# Multiplexer_Bank.net
KiCad netlist of a schematic drawn in Altium Designer
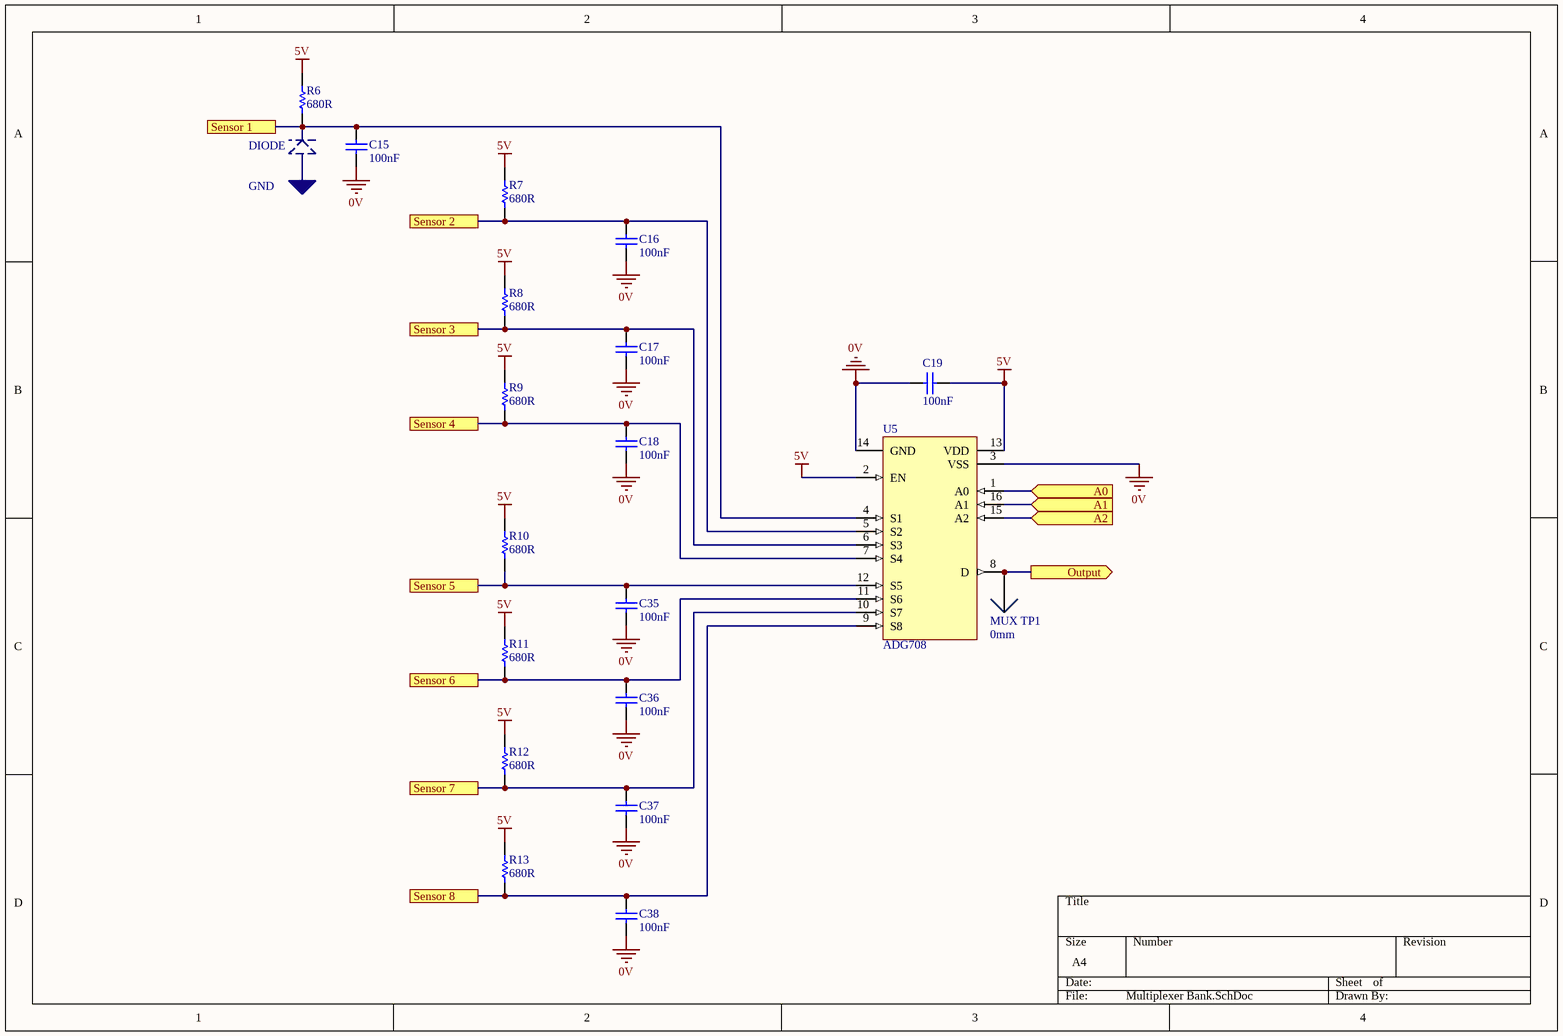
[diagram p0: Multiplexer Bank.SchDoc]

(export (version "E")
  (design (tool "Eeschema 10.0.6"))
  (components
    (comp (ref "C15")
      (value "100nF")
      (footprint "0805")
      (fields
        (field (name "PART NUMBER") "GCM21BR71E104KA37L")
        (field (name "TOLERANCE") "10%")
        (field (name "MANUFACTURER") "muRata")
      )
      (libsource (lib "ts_20-standard-library") (part "Capacitor"))
    )
    (comp (ref "C16")
      (value "100nF")
      (footprint "0805")
      (fields
        (field (name "PART NUMBER") "GCM21BR71E104KA37L")
        (field (name "TOLERANCE") "10%")
        (field (name "MANUFACTURER") "muRata")
      )
      (libsource (lib "ts_20-standard-library") (part "Capacitor"))
    )
    (comp (ref "C17")
      (value "100nF")
      (footprint "0805")
      (fields
        (field (name "PART NUMBER") "GCM21BR71E104KA37L")
        (field (name "TOLERANCE") "10%")
        (field (name "MANUFACTURER") "muRata")
      )
      (libsource (lib "ts_20-standard-library") (part "Capacitor"))
    )
    (comp (ref "C18")
      (value "100nF")
      (footprint "0805")
      (fields
        (field (name "PART NUMBER") "GCM21BR71E104KA37L")
        (field (name "TOLERANCE") "10%")
        (field (name "MANUFACTURER") "muRata")
      )
      (libsource (lib "ts_20-standard-library") (part "Capacitor"))
    )
    (comp (ref "C19")
      (value "100nF")
      (footprint "0805")
      (fields
        (field (name "PART NUMBER") "GCM21BR71E104KA37L")
        (field (name "TOLERANCE") "10%")
        (field (name "MANUFACTURER") "muRata")
      )
      (libsource (lib "ts_20-standard-library") (part "Capacitor"))
    )
    (comp (ref "C35")
      (value "100nF")
      (footprint "0805")
      (fields
        (field (name "PART NUMBER") "GCM21BR71E104KA37L")
        (field (name "TOLERANCE") "10%")
        (field (name "MANUFACTURER") "muRata")
      )
      (libsource (lib "ts_20-standard-library") (part "Capacitor"))
    )
    (comp (ref "C36")
      (value "100nF")
      (footprint "0805")
      (fields
        (field (name "PART NUMBER") "GCM21BR71E104KA37L")
        (field (name "TOLERANCE") "10%")
        (field (name "MANUFACTURER") "muRata")
      )
      (libsource (lib "ts_20-standard-library") (part "Capacitor"))
    )
    (comp (ref "C37")
      (value "100nF")
      (footprint "0805")
      (fields
        (field (name "PART NUMBER") "GCM21BR71E104KA37L")
        (field (name "TOLERANCE") "10%")
        (field (name "MANUFACTURER") "muRata")
      )
      (libsource (lib "ts_20-standard-library") (part "Capacitor"))
    )
    (comp (ref "C38")
      (value "100nF")
      (footprint "0805")
      (fields
        (field (name "PART NUMBER") "GCM21BR71E104KA37L")
        (field (name "TOLERANCE") "10%")
        (field (name "MANUFACTURER") "muRata")
      )
      (libsource (lib "ts_20-standard-library") (part "Capacitor"))
    )
    (comp (ref "MUX TP1")
      (value "0mm")
      (footprint "SMD Test Point")
      (fields (field (name "PART NUMBER") "SMD Test Point") (field (name "CONTACT") "NA"))
      (libsource (lib "ts_20-standard-connectors") (part "Test Point"))
    )
    (comp (ref "R6")
      (value "680R")
      (footprint "0805")
      (fields
        (field (name "PART NUMBER") "RC0805FR07680RL")
        (field (name "MANUFACTURER") "YAGEO")
        (field (name "TOLERANCE") "0.01")
      )
      (libsource (lib "ts_20-standard-library") (part "Resistor"))
    )
    (comp (ref "R7")
      (value "680R")
      (footprint "0805")
      (fields
        (field (name "PART NUMBER") "RC0805FR07680RL")
        (field (name "MANUFACTURER") "YAGEO")
        (field (name "TOLERANCE") "0.01")
      )
      (libsource (lib "ts_20-standard-library") (part "Resistor"))
    )
    (comp (ref "R8")
      (value "680R")
      (footprint "0805")
      (fields
        (field (name "PART NUMBER") "RC0805FR07680RL")
        (field (name "MANUFACTURER") "YAGEO")
        (field (name "TOLERANCE") "0.01")
      )
      (libsource (lib "ts_20-standard-library") (part "Resistor"))
    )
    (comp (ref "R9")
      (value "680R")
      (footprint "0805")
      (fields
        (field (name "PART NUMBER") "RC0805FR07680RL")
        (field (name "MANUFACTURER") "YAGEO")
        (field (name "TOLERANCE") "0.01")
      )
      (libsource (lib "ts_20-standard-library") (part "Resistor"))
    )
    (comp (ref "R10")
      (value "680R")
      (footprint "0805")
      (fields
        (field (name "PART NUMBER") "RC0805FR07680RL")
        (field (name "MANUFACTURER") "YAGEO")
        (field (name "TOLERANCE") "0.01")
      )
      (libsource (lib "ts_20-standard-library") (part "Resistor"))
    )
    (comp (ref "R11")
      (value "680R")
      (footprint "0805")
      (fields
        (field (name "PART NUMBER") "RC0805FR07680RL")
        (field (name "MANUFACTURER") "YAGEO")
        (field (name "TOLERANCE") "0.01")
      )
      (libsource (lib "ts_20-standard-library") (part "Resistor"))
    )
    (comp (ref "R12")
      (value "680R")
      (footprint "0805")
      (fields
        (field (name "PART NUMBER") "RC0805FR07680RL")
        (field (name "MANUFACTURER") "YAGEO")
        (field (name "TOLERANCE") "0.01")
      )
      (libsource (lib "ts_20-standard-library") (part "Resistor"))
    )
    (comp (ref "R13")
      (value "680R")
      (footprint "0805")
      (fields
        (field (name "PART NUMBER") "RC0805FR07680RL")
        (field (name "MANUFACTURER") "YAGEO")
        (field (name "TOLERANCE") "0.01")
      )
      (libsource (lib "ts_20-standard-library") (part "Resistor"))
    )
    (comp (ref "U5")
      (value "ADG708")
      (footprint "AD 16-TSSOP")
      (description "1 Circuit IC Switch 8:1 4.5Ohm 16-TSSOP")
      (fields
        (field (name "MANUFACTURER") "Analog Devices")
        (field (name "DIGIKEY PART NUMBER") "ADG708BRUZ-ND")
      )
      (libsource (lib "ts_20-standard-library") (part "ADG708"))
    )
  )
  (nets
    (net (code "1") (name "/A0") (class "Default")
      (node (ref "U5") (pin "1") (pinfunction "A0_1") (pintype "input"))
    )
    (net (code "2") (name "/A1") (class "Default")
      (node (ref "U5") (pin "16") (pinfunction "A1_16") (pintype "input"))
    )
    (net (code "3") (name "/A2") (class "Default")
      (node (ref "U5") (pin "15") (pinfunction "A2_15") (pintype "input"))
    )
    (net (code "4") (name "/Output") (class "Default")
      (node (ref "MUX TP1") (pin "1") (pinfunction "1_1") (pintype "passive"))
      (node (ref "U5") (pin "8") (pinfunction "D_8") (pintype "output"))
    )
    (net (code "5") (name "/Sensor 1") (class "Default")
      (node (ref "C15") (pin "2") (pinfunction "2_2") (pintype "passive"))
      (node (ref "R6") (pin "1") (pinfunction "1_1") (pintype "passive"))
      (node (ref "U5") (pin "4") (pinfunction "S1_4") (pintype "input"))
    )
    (net (code "6") (name "/Sensor 2") (class "Default")
      (node (ref "C16") (pin "2") (pinfunction "2_2") (pintype "passive"))
      (node (ref "R7") (pin "1") (pinfunction "1_1") (pintype "passive"))
      (node (ref "U5") (pin "5") (pinfunction "S2_5") (pintype "input"))
    )
    (net (code "7") (name "/Sensor 3") (class "Default")
      (node (ref "C17") (pin "2") (pinfunction "2_2") (pintype "passive"))
      (node (ref "R8") (pin "1") (pinfunction "1_1") (pintype "passive"))
      (node (ref "U5") (pin "6") (pinfunction "S3_6") (pintype "input"))
    )
    (net (code "8") (name "/Sensor 4") (class "Default")
      (node (ref "C18") (pin "2") (pinfunction "2_2") (pintype "passive"))
      (node (ref "R9") (pin "1") (pinfunction "1_1") (pintype "passive"))
      (node (ref "U5") (pin "7") (pinfunction "S4_7") (pintype "input"))
    )
    (net (code "9") (name "/Sensor 5") (class "Default")
      (node (ref "C35") (pin "2") (pinfunction "2_2") (pintype "passive"))
      (node (ref "R10") (pin "1") (pinfunction "1_1") (pintype "passive"))
      (node (ref "U5") (pin "12") (pinfunction "S5_12") (pintype "input"))
    )
    (net (code "10") (name "/Sensor 6") (class "Default")
      (node (ref "C36") (pin "2") (pinfunction "2_2") (pintype "passive"))
      (node (ref "R11") (pin "1") (pinfunction "1_1") (pintype "passive"))
      (node (ref "U5") (pin "11") (pinfunction "S6_11") (pintype "input"))
    )
    (net (code "11") (name "/Sensor 7") (class "Default")
      (node (ref "C37") (pin "2") (pinfunction "2_2") (pintype "passive"))
      (node (ref "R12") (pin "1") (pinfunction "1_1") (pintype "passive"))
      (node (ref "U5") (pin "10") (pinfunction "S7_10") (pintype "input"))
    )
    (net (code "12") (name "/Sensor 8") (class "Default")
      (node (ref "C38") (pin "2") (pinfunction "2_2") (pintype "passive"))
      (node (ref "R13") (pin "1") (pinfunction "1_1") (pintype "passive"))
      (node (ref "U5") (pin "9") (pinfunction "S8_9") (pintype "input"))
    )
    (net (code "13") (name "0V") (class "Default")
      (node (ref "C15") (pin "1") (pinfunction "1_1") (pintype "passive"))
      (node (ref "C16") (pin "1") (pinfunction "1_1") (pintype "passive"))
      (node (ref "C17") (pin "1") (pinfunction "1_1") (pintype "passive"))
      (node (ref "C18") (pin "1") (pinfunction "1_1") (pintype "passive"))
      (node (ref "C19") (pin "1") (pinfunction "1_1") (pintype "passive"))
      (node (ref "C35") (pin "1") (pinfunction "1_1") (pintype "passive"))
      (node (ref "C36") (pin "1") (pinfunction "1_1") (pintype "passive"))
      (node (ref "C37") (pin "1") (pinfunction "1_1") (pintype "passive"))
      (node (ref "C38") (pin "1") (pinfunction "1_1") (pintype "passive"))
      (node (ref "U5") (pin "14") (pinfunction "GND_14") (pintype "power_in"))
      (node (ref "U5") (pin "3") (pinfunction "VSS_3") (pintype "power_in"))
    )
    (net (code "14") (name "5V") (class "Default")
      (node (ref "C19") (pin "2") (pinfunction "2_2") (pintype "passive"))
      (node (ref "R10") (pin "2") (pinfunction "2_2") (pintype "passive"))
      (node (ref "R11") (pin "2") (pinfunction "2_2") (pintype "passive"))
      (node (ref "R12") (pin "2") (pinfunction "2_2") (pintype "passive"))
      (node (ref "R13") (pin "2") (pinfunction "2_2") (pintype "passive"))
      (node (ref "R6") (pin "2") (pinfunction "2_2") (pintype "passive"))
      (node (ref "R7") (pin "2") (pinfunction "2_2") (pintype "passive"))
      (node (ref "R8") (pin "2") (pinfunction "2_2") (pintype "passive"))
      (node (ref "R9") (pin "2") (pinfunction "2_2") (pintype "passive"))
      (node (ref "U5") (pin "13") (pinfunction "VDD_13") (pintype "power_in"))
      (node (ref "U5") (pin "2") (pinfunction "EN_2") (pintype "input"))
    )
  )
)
